# resistor-pull-up-down.net
KiCad netlist of a schematic drawn in EAGLE
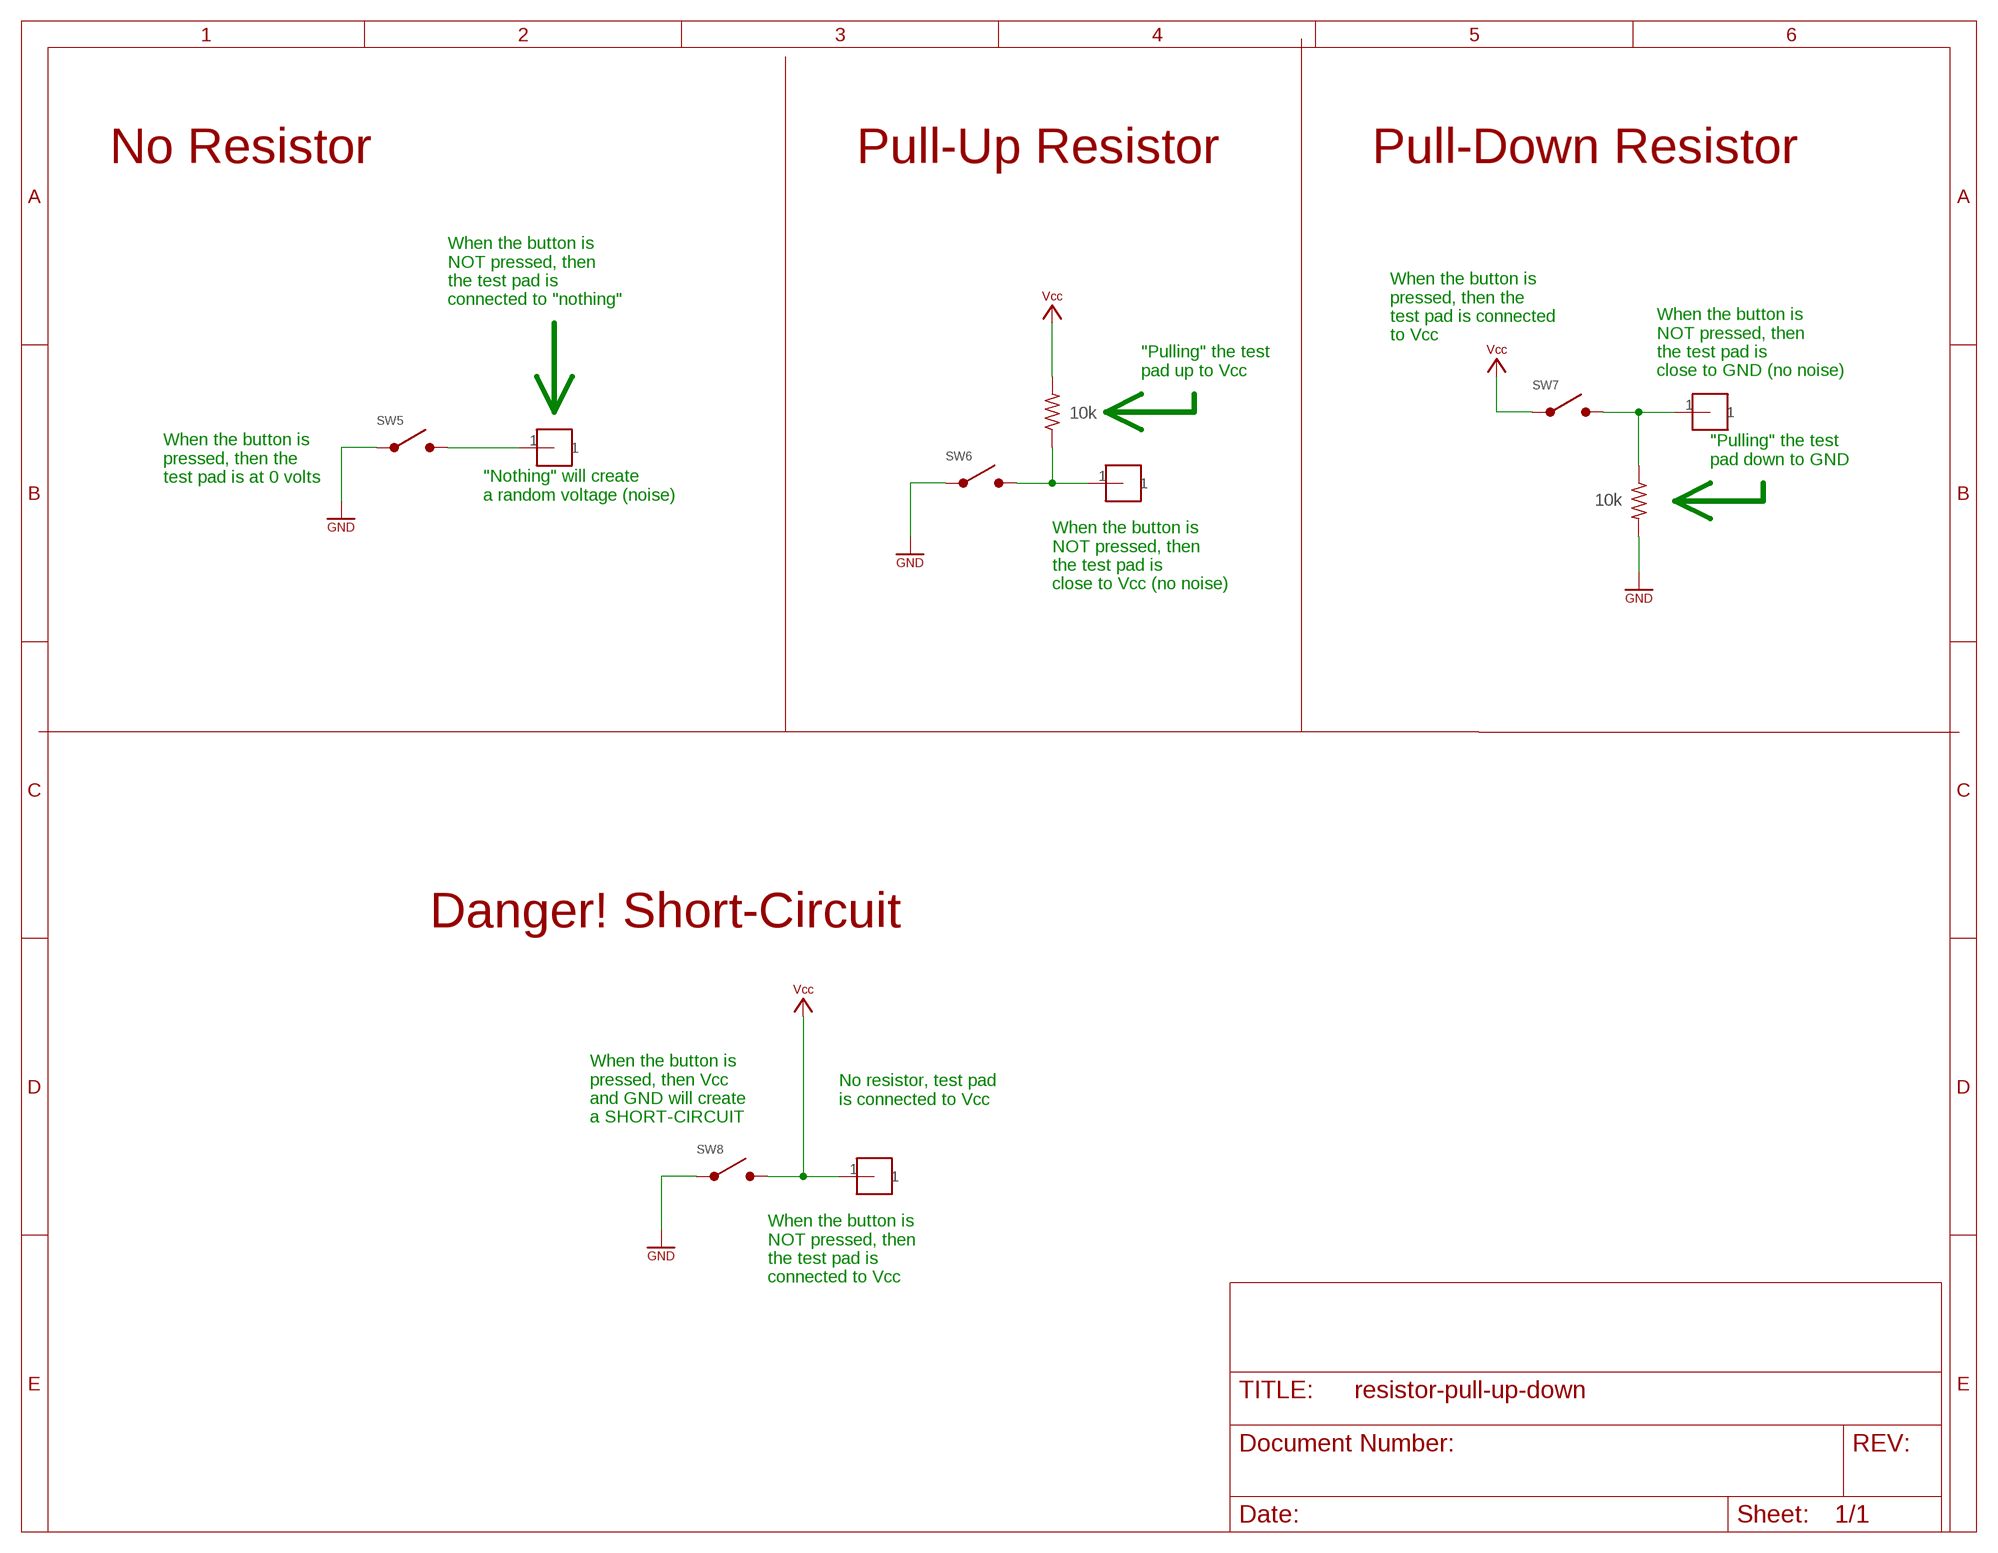
[diagram p0: schematic, sheet 1]

(export (version "E")
  (design (tool "Eeschema 10.0.6"))
  (components
    (comp (ref "R1")
      (value "10k")
      (footprint "eagle-import:R0603")
      (libsource (lib "eagle-import") (part "R-US_R0603"))
    )
    (comp (ref "R2")
      (value "10k")
      (footprint "eagle-import:R0603")
      (libsource (lib "eagle-import") (part "R-US_R0603"))
    )
    (comp (ref "SW5")
      (value "SWITCH_BUTTON_SPST")
      (footprint "eagle-import:7914G-1-000E")
      (libsource (lib "eagle-import") (part "SWITCH_BUTTON_SPST"))
    )
    (comp (ref "SW6")
      (value "SWITCH_BUTTON_SPST")
      (footprint "eagle-import:7914G-1-000E")
      (libsource (lib "eagle-import") (part "SWITCH_BUTTON_SPST"))
    )
    (comp (ref "SW7")
      (value "SWITCH_BUTTON_SPST")
      (footprint "eagle-import:7914G-1-000E")
      (libsource (lib "eagle-import") (part "SWITCH_BUTTON_SPST"))
    )
    (comp (ref "SW8")
      (value "SWITCH_BUTTON_SPST")
      (footprint "eagle-import:7914G-1-000E")
      (libsource (lib "eagle-import") (part "SWITCH_BUTTON_SPST"))
    )
    (comp (ref "U$1")
      (value "HEADER-1-TESTPOINT")
      (footprint "eagle-import:TESTPOINT-1")
      (libsource (lib "eagle-import") (part "HEADER-1-TESTPOINT"))
    )
    (comp (ref "U$2")
      (value "HEADER-1-TESTPOINT")
      (footprint "eagle-import:TESTPOINT-1")
      (libsource (lib "eagle-import") (part "HEADER-1-TESTPOINT"))
    )
    (comp (ref "U$3")
      (value "HEADER-1-TESTPOINT")
      (footprint "eagle-import:TESTPOINT-1")
      (libsource (lib "eagle-import") (part "HEADER-1-TESTPOINT"))
    )
    (comp (ref "U$4")
      (value "HEADER-1-TESTPOINT")
      (footprint "eagle-import:TESTPOINT-1")
      (libsource (lib "eagle-import") (part "HEADER-1-TESTPOINT"))
    )
  )
  (nets
    (net (code "3") (name "Net-(R1-Pad1)") (class "Default")
      (node (ref "R1") (pin "1") (pinfunction "1_1") (pintype "passive"))
      (node (ref "SW6") (pin "2A") (pinfunction "2_2A") (pintype "bidirectional"))
      (node (ref "SW6") (pin "2B") (pinfunction "2_2B") (pintype "bidirectional"))
      (node (ref "U$2") (pin "1") (pinfunction "1_1") (pintype "bidirectional"))
    )
    (net (code "4") (name "Net-(R2-Pad1)") (class "Default")
      (node (ref "R2") (pin "1") (pinfunction "1_1") (pintype "passive"))
      (node (ref "SW7") (pin "2A") (pinfunction "2_2A") (pintype "bidirectional"))
      (node (ref "SW7") (pin "2B") (pinfunction "2_2B") (pintype "bidirectional"))
      (node (ref "U$3") (pin "1") (pinfunction "1_1") (pintype "bidirectional"))
    )
    (net (code "5") (name "Net-(SW5-2-Pad2A)") (class "Default")
      (node (ref "SW5") (pin "2A") (pinfunction "2_2A") (pintype "bidirectional"))
      (node (ref "SW5") (pin "2B") (pinfunction "2_2B") (pintype "bidirectional"))
      (node (ref "U$1") (pin "1") (pinfunction "1_1") (pintype "bidirectional"))
    )
    (net (code "6") (name "SYMBOL_GND") (class "Default")
      (node (ref "R2") (pin "2") (pinfunction "2_2") (pintype "passive"))
      (node (ref "SW5") (pin "1A") (pinfunction "1_1A") (pintype "bidirectional"))
      (node (ref "SW5") (pin "1B") (pinfunction "1_1B") (pintype "bidirectional"))
      (node (ref "SW6") (pin "1A") (pinfunction "1_1A") (pintype "bidirectional"))
      (node (ref "SW6") (pin "1B") (pinfunction "1_1B") (pintype "bidirectional"))
      (node (ref "SW8") (pin "1A") (pinfunction "1_1A") (pintype "bidirectional"))
      (node (ref "SW8") (pin "1B") (pinfunction "1_1B") (pintype "bidirectional"))
    )
    (net (code "7") (name "SYMBOL_VCC") (class "Default")
      (node (ref "R1") (pin "2") (pinfunction "2_2") (pintype "passive"))
      (node (ref "SW7") (pin "1A") (pinfunction "1_1A") (pintype "bidirectional"))
      (node (ref "SW7") (pin "1B") (pinfunction "1_1B") (pintype "bidirectional"))
      (node (ref "SW8") (pin "2A") (pinfunction "2_2A") (pintype "bidirectional"))
      (node (ref "SW8") (pin "2B") (pinfunction "2_2B") (pintype "bidirectional"))
      (node (ref "U$4") (pin "1") (pinfunction "1_1") (pintype "bidirectional"))
    )
  )
)
